# PCB-ARD-BOS2.net
KiCad netlist of a schematic drawn in EAGLE
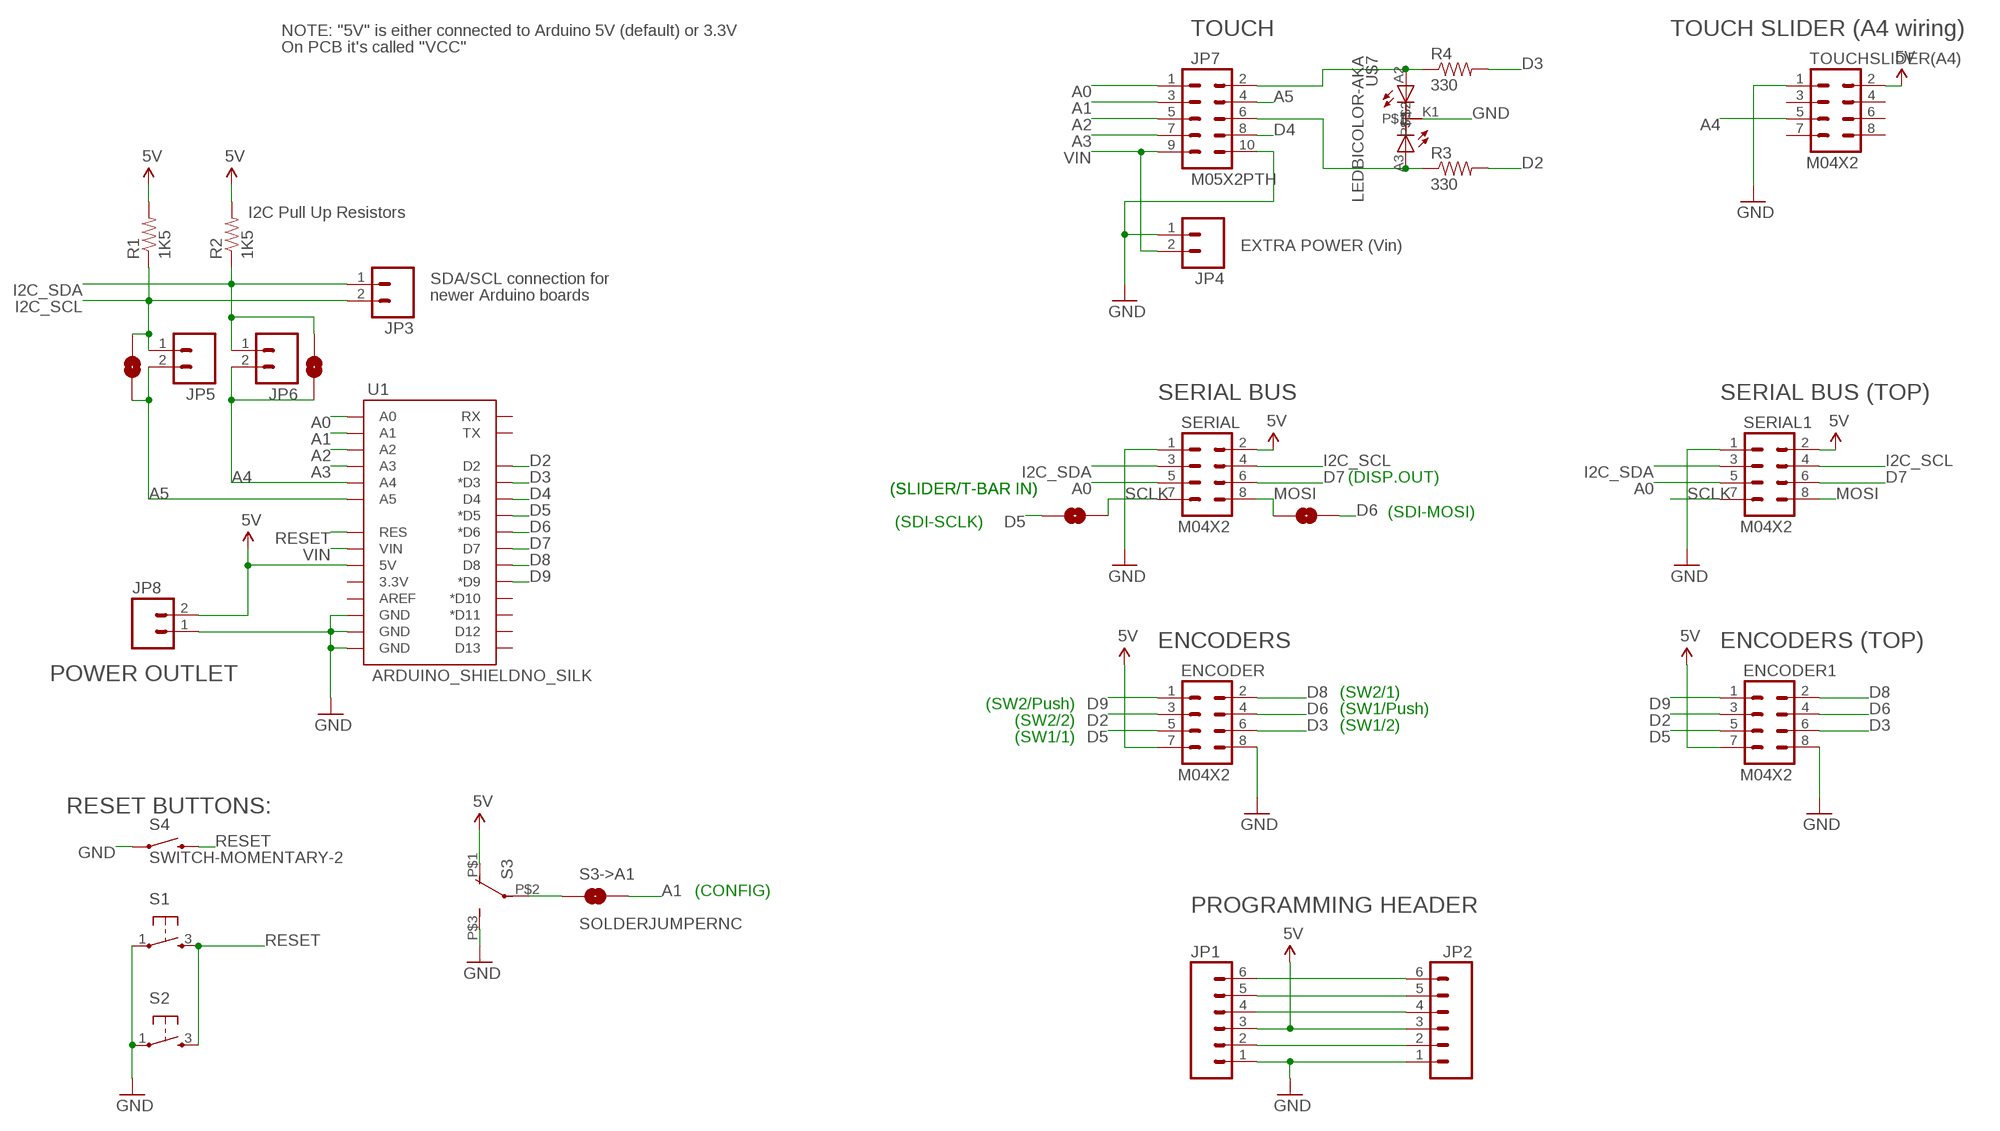
[diagram p0: schematic, sheet 1]

(export (version "E")
  (design (tool "Eeschema 10.0.6"))
  (components
    (comp (ref "ENCODER")
      (value "M04X2")
      (footprint "eagle-import:2X4")
      (libsource (lib "eagle-import") (part "M04X2"))
    )
    (comp (ref "ENCODER1")
      (value "M04X2")
      (footprint "eagle-import:2X4")
      (libsource (lib "eagle-import") (part "M04X2"))
    )
    (comp (ref "JP1")
      (value "M06POLAR")
      (footprint "eagle-import:MOLEX-1X6")
      (libsource (lib "eagle-import") (part "M06POLAR"))
    )
    (comp (ref "JP2")
      (value "M06POLAR")
      (footprint "eagle-import:MOLEX-1X6")
      (libsource (lib "eagle-import") (part "M06POLAR"))
    )
    (comp (ref "JP3")
      (value "M02PTH")
      (footprint "eagle-import:1X02")
      (libsource (lib "eagle-import") (part "M02PTH"))
    )
    (comp (ref "JP4")
      (value "M02PTH")
      (footprint "eagle-import:1X02")
      (libsource (lib "eagle-import") (part "M02PTH"))
    )
    (comp (ref "JP5")
      (value "M02PTH")
      (footprint "eagle-import:1X02")
      (libsource (lib "eagle-import") (part "M02PTH"))
    )
    (comp (ref "JP6")
      (value "M02PTH")
      (footprint "eagle-import:1X02")
      (libsource (lib "eagle-import") (part "M02PTH"))
    )
    (comp (ref "JP7")
      (value "M05X2PTH")
      (footprint "eagle-import:AVR_ICSP")
      (libsource (lib "eagle-import") (part "M05X2PTH"))
    )
    (comp (ref "JP8")
      (value "M02PTH4")
      (footprint "eagle-import:1X02_XTRA_BIG")
      (libsource (lib "eagle-import") (part "M02PTH4"))
    )
    (comp (ref "MOSI->D6")
      (value "SOLDERJUMPERNC")
      (footprint "eagle-import:SJ_2S")
      (libsource (lib "eagle-import") (part "SOLDERJUMPERNC"))
    )
    (comp (ref "R1")
      (value "1K5")
      (footprint "eagle-import:0603-RES")
      (libsource (lib "eagle-import") (part "RESISTOR0603-RES"))
    )
    (comp (ref "R2")
      (value "1K5")
      (footprint "eagle-import:0603-RES")
      (libsource (lib "eagle-import") (part "RESISTOR0603-RES"))
    )
    (comp (ref "R3")
      (value "330")
      (footprint "eagle-import:AXIAL-0.4")
      (libsource (lib "eagle-import") (part "RESISTORPTH-1/4W"))
    )
    (comp (ref "R4")
      (value "330")
      (footprint "eagle-import:AXIAL-0.4")
      (libsource (lib "eagle-import") (part "RESISTORPTH-1/4W"))
    )
    (comp (ref "S1")
      (value "TAC_SWITCH")
      (footprint "eagle-import:PUSHBUTTON")
      (libsource (lib "eagle-import") (part "TAC_SWITCH"))
    )
    (comp (ref "S2")
      (value "TAC_SWITCH")
      (footprint "eagle-import:PUSHBUTTON")
      (libsource (lib "eagle-import") (part "TAC_SWITCH"))
    )
    (comp (ref "S3")
      (value "SWITCH-DPST")
      (footprint "eagle-import:TECONNECTIVITY-DPST")
      (libsource (lib "eagle-import") (part "SWITCH-DPST"))
    )
    (comp (ref "S3->A1")
      (value "SOLDERJUMPERNC")
      (footprint "eagle-import:SJ_2S")
      (libsource (lib "eagle-import") (part "SOLDERJUMPERNC"))
    )
    (comp (ref "S3->A2")
      (value "SOLDERJUMPERNC")
      (footprint "eagle-import:SJ_2S")
      (libsource (lib "eagle-import") (part "SOLDERJUMPERNC"))
    )
    (comp (ref "S3->A3")
      (value "SOLDERJUMPERNC")
      (footprint "eagle-import:SJ_2S")
      (libsource (lib "eagle-import") (part "SOLDERJUMPERNC"))
    )
    (comp (ref "S4")
      (value "SWITCH-MOMENTARY-2")
      (footprint "eagle-import:TACTILE_SWITCH_TALL")
      (libsource (lib "eagle-import") (part "SWITCH-MOMENTARY-2"))
    )
    (comp (ref "SCLK->D5")
      (value "SOLDERJUMPERNC")
      (footprint "eagle-import:SJ_2S")
      (libsource (lib "eagle-import") (part "SOLDERJUMPERNC"))
    )
    (comp (ref "SERIAL")
      (value "M04X2")
      (footprint "eagle-import:2X4")
      (libsource (lib "eagle-import") (part "M04X2"))
    )
    (comp (ref "SERIAL1")
      (value "M04X2")
      (footprint "eagle-import:2X4")
      (libsource (lib "eagle-import") (part "M04X2"))
    )
    (comp (ref "TOUCHSLIDER(A4)")
      (value "M04X2")
      (footprint "eagle-import:2X4")
      (libsource (lib "eagle-import") (part "M04X2"))
    )
    (comp (ref "U$7")
      (value "LEDBICOLOR-AKA")
      (footprint "eagle-import:LED5MM-BICOLOR")
      (libsource (lib "eagle-import") (part "LEDBICOLOR-AKA"))
    )
    (comp (ref "U1")
      (value "ARDUINO_SHIELDNO_SILK")
      (footprint "eagle-import:DUEMILANOVE_VIAS")
      (libsource (lib "eagle-import") (part "ARDUINO_SHIELDNO_SILK"))
    )
  )
  (nets
    (net (code "1") (name "/A0") (class "Default")
      (node (ref "JP7") (pin "1") (pinfunction "1_1") (pintype "passive"))
      (node (ref "SERIAL") (pin "5") (pinfunction "5_5") (pintype "passive"))
      (node (ref "SERIAL1") (pin "5") (pinfunction "5_5") (pintype "passive"))
      (node (ref "U1") (pin "A0") (pinfunction "A0_A0") (pintype "bidirectional"))
    )
    (net (code "2") (name "/A1") (class "Default")
      (node (ref "JP7") (pin "3") (pinfunction "3_3") (pintype "passive"))
      (node (ref "S3->A1") (pin "2") (pinfunction "2_2") (pintype "passive"))
      (node (ref "U1") (pin "A1") (pinfunction "A1_A1") (pintype "bidirectional"))
    )
    (net (code "3") (name "/A2") (class "Default")
      (node (ref "JP7") (pin "5") (pinfunction "5_5") (pintype "passive"))
      (node (ref "U1") (pin "A2") (pinfunction "A2_A2") (pintype "bidirectional"))
    )
    (net (code "4") (name "/A3") (class "Default")
      (node (ref "JP7") (pin "7") (pinfunction "7_7") (pintype "passive"))
      (node (ref "U1") (pin "A3") (pinfunction "A3_A3") (pintype "bidirectional"))
    )
    (net (code "5") (name "/A4") (class "Default")
      (node (ref "JP6") (pin "2") (pinfunction "2_2") (pintype "passive"))
      (node (ref "S3->A3") (pin "2") (pinfunction "2_2") (pintype "passive"))
      (node (ref "TOUCHSLIDER(A4)") (pin "5") (pinfunction "5_5") (pintype "passive"))
      (node (ref "U1") (pin "A4") (pinfunction "A4_A4") (pintype "bidirectional"))
    )
    (net (code "6") (name "/A5") (class "Default")
      (node (ref "JP5") (pin "2") (pinfunction "2_2") (pintype "passive"))
      (node (ref "JP7") (pin "4") (pinfunction "4_4") (pintype "passive"))
      (node (ref "S3->A2") (pin "2") (pinfunction "2_2") (pintype "passive"))
      (node (ref "U1") (pin "A5") (pinfunction "A5_A5") (pintype "bidirectional"))
    )
    (net (code "7") (name "/D2") (class "Default")
      (node (ref "ENCODER") (pin "3") (pinfunction "3_3") (pintype "passive"))
      (node (ref "ENCODER1") (pin "3") (pinfunction "3_3") (pintype "passive"))
      (node (ref "R3") (pin "P$2") (pinfunction "2_P$2") (pintype "passive"))
      (node (ref "U1") (pin "D2") (pinfunction "D2_D2") (pintype "bidirectional"))
    )
    (net (code "8") (name "/D3") (class "Default")
      (node (ref "ENCODER") (pin "6") (pinfunction "6_6") (pintype "passive"))
      (node (ref "ENCODER1") (pin "6") (pinfunction "6_6") (pintype "passive"))
      (node (ref "R4") (pin "P$2") (pinfunction "2_P$2") (pintype "passive"))
      (node (ref "U1") (pin "D3") (pinfunction "*D3_D3") (pintype "bidirectional"))
    )
    (net (code "9") (name "/D4") (class "Default")
      (node (ref "JP7") (pin "8") (pinfunction "8_8") (pintype "passive"))
      (node (ref "U1") (pin "D4") (pinfunction "D4_D4") (pintype "bidirectional"))
    )
    (net (code "10") (name "/D5") (class "Default")
      (node (ref "ENCODER") (pin "5") (pinfunction "5_5") (pintype "passive"))
      (node (ref "ENCODER1") (pin "5") (pinfunction "5_5") (pintype "passive"))
      (node (ref "SCLK->D5") (pin "1") (pinfunction "1_1") (pintype "passive"))
      (node (ref "U1") (pin "D5") (pinfunction "*D5_D5") (pintype "bidirectional"))
    )
    (net (code "11") (name "/D6") (class "Default")
      (node (ref "ENCODER") (pin "4") (pinfunction "4_4") (pintype "passive"))
      (node (ref "ENCODER1") (pin "4") (pinfunction "4_4") (pintype "passive"))
      (node (ref "MOSI->D6") (pin "2") (pinfunction "2_2") (pintype "passive"))
      (node (ref "U1") (pin "D6") (pinfunction "*D6_D6") (pintype "bidirectional"))
    )
    (net (code "12") (name "/D7") (class "Default")
      (node (ref "SERIAL") (pin "6") (pinfunction "6_6") (pintype "passive"))
      (node (ref "SERIAL1") (pin "6") (pinfunction "6_6") (pintype "passive"))
      (node (ref "U1") (pin "D7") (pinfunction "D7_D7") (pintype "bidirectional"))
    )
    (net (code "13") (name "/D8") (class "Default")
      (node (ref "ENCODER") (pin "2") (pinfunction "2_2") (pintype "passive"))
      (node (ref "ENCODER1") (pin "2") (pinfunction "2_2") (pintype "passive"))
      (node (ref "U1") (pin "D8") (pinfunction "D8_D8") (pintype "bidirectional"))
    )
    (net (code "14") (name "/D9") (class "Default")
      (node (ref "ENCODER") (pin "1") (pinfunction "1_1") (pintype "passive"))
      (node (ref "ENCODER1") (pin "1") (pinfunction "1_1") (pintype "passive"))
      (node (ref "U1") (pin "D9") (pinfunction "*D9_D9") (pintype "bidirectional"))
    )
    (net (code "15") (name "/I2C_SCL") (class "Default")
      (node (ref "JP3") (pin "2") (pinfunction "2_2") (pintype "passive"))
      (node (ref "JP5") (pin "1") (pinfunction "1_1") (pintype "passive"))
      (node (ref "R1") (pin "1") (pinfunction "1_1") (pintype "passive"))
      (node (ref "S3->A2") (pin "1") (pinfunction "1_1") (pintype "passive"))
      (node (ref "SERIAL") (pin "4") (pinfunction "4_4") (pintype "passive"))
      (node (ref "SERIAL1") (pin "4") (pinfunction "4_4") (pintype "passive"))
    )
    (net (code "16") (name "/I2C_SDA") (class "Default")
      (node (ref "JP3") (pin "1") (pinfunction "1_1") (pintype "passive"))
      (node (ref "JP6") (pin "1") (pinfunction "1_1") (pintype "passive"))
      (node (ref "R2") (pin "1") (pinfunction "1_1") (pintype "passive"))
      (node (ref "S3->A3") (pin "1") (pinfunction "1_1") (pintype "passive"))
      (node (ref "SERIAL") (pin "3") (pinfunction "3_3") (pintype "passive"))
      (node (ref "SERIAL1") (pin "3") (pinfunction "3_3") (pintype "passive"))
    )
    (net (code "17") (name "/MOSI") (class "Default")
      (node (ref "MOSI->D6") (pin "1") (pinfunction "1_1") (pintype "passive"))
      (node (ref "SERIAL") (pin "8") (pinfunction "8_8") (pintype "passive"))
      (node (ref "SERIAL1") (pin "8") (pinfunction "8_8") (pintype "passive"))
    )
    (net (code "18") (name "/RESET") (class "Default")
      (node (ref "S1") (pin "3") (pinfunction "3_3") (pintype "passive"))
      (node (ref "S2") (pin "3") (pinfunction "3_3") (pintype "passive"))
      (node (ref "S4") (pin "B2") (pinfunction "2_B2") (pintype "passive"))
      (node (ref "U1") (pin "RES") (pinfunction "RES_RES") (pintype "bidirectional"))
    )
    (net (code "19") (name "/SCLK") (class "Default")
      (node (ref "SCLK->D5") (pin "2") (pinfunction "2_2") (pintype "passive"))
      (node (ref "SERIAL") (pin "7") (pinfunction "7_7") (pintype "passive"))
      (node (ref "SERIAL1") (pin "7") (pinfunction "7_7") (pintype "passive"))
    )
    (net (code "20") (name "/VIN") (class "Default")
      (node (ref "JP4") (pin "2") (pinfunction "2_2") (pintype "passive"))
      (node (ref "JP7") (pin "9") (pinfunction "9_9") (pintype "passive"))
      (node (ref "U1") (pin "VIN") (pinfunction "VIN_VIN") (pintype "bidirectional"))
    )
    (net (code "21") (name "5V") (class "Default")
      (node (ref "ENCODER") (pin "7") (pinfunction "7_7") (pintype "passive"))
      (node (ref "ENCODER1") (pin "7") (pinfunction "7_7") (pintype "passive"))
      (node (ref "JP1") (pin "3") (pinfunction "3_3") (pintype "passive"))
      (node (ref "JP2") (pin "3") (pinfunction "3_3") (pintype "passive"))
      (node (ref "JP8") (pin "2") (pinfunction "2_2") (pintype "passive"))
      (node (ref "R1") (pin "2") (pinfunction "2_2") (pintype "passive"))
      (node (ref "R2") (pin "2") (pinfunction "2_2") (pintype "passive"))
      (node (ref "S3") (pin "P$1") (pinfunction "O_P$1") (pintype "passive"))
      (node (ref "SERIAL") (pin "2") (pinfunction "2_2") (pintype "passive"))
      (node (ref "SERIAL1") (pin "2") (pinfunction "2_2") (pintype "passive"))
      (node (ref "TOUCHSLIDER(A4)") (pin "2") (pinfunction "2_2") (pintype "passive"))
      (node (ref "U1") (pin "5V") (pinfunction "5V_5V") (pintype "bidirectional"))
    )
    (net (code "22") (name "GND") (class "Default")
      (node (ref "ENCODER") (pin "8") (pinfunction "8_8") (pintype "passive"))
      (node (ref "ENCODER1") (pin "8") (pinfunction "8_8") (pintype "passive"))
      (node (ref "JP1") (pin "1") (pinfunction "1_1") (pintype "passive"))
      (node (ref "JP2") (pin "1") (pinfunction "1_1") (pintype "passive"))
      (node (ref "JP4") (pin "1") (pinfunction "1_1") (pintype "passive"))
      (node (ref "JP7") (pin "10") (pinfunction "10_10") (pintype "passive"))
      (node (ref "JP8") (pin "1") (pinfunction "1_1") (pintype "passive"))
      (node (ref "S1") (pin "1") (pinfunction "1_1") (pintype "passive"))
      (node (ref "S2") (pin "1") (pinfunction "1_1") (pintype "passive"))
      (node (ref "S3") (pin "P$3") (pinfunction "S_P$3") (pintype "passive"))
      (node (ref "S4") (pin "A2") (pinfunction "1_A2") (pintype "passive"))
      (node (ref "SERIAL") (pin "1") (pinfunction "1_1") (pintype "passive"))
      (node (ref "SERIAL1") (pin "1") (pinfunction "1_1") (pintype "passive"))
      (node (ref "TOUCHSLIDER(A4)") (pin "1") (pinfunction "1_1") (pintype "passive"))
      (node (ref "U$7") (pin "K1") (pinfunction "P$1_K1") (pintype "bidirectional"))
      (node (ref "U1") (pin "GND@0") (pinfunction "GND_GND@0") (pintype "bidirectional"))
      (node (ref "U1") (pin "GND@1") (pinfunction "GND_GND@1") (pintype "bidirectional"))
      (node (ref "U1") (pin "GND@2") (pinfunction "GND_GND@2") (pintype "bidirectional"))
    )
    (net (code "23") (name "Net-(JP1-Pad2)") (class "Default")
      (node (ref "JP1") (pin "2") (pinfunction "2_2") (pintype "passive"))
      (node (ref "JP2") (pin "2") (pinfunction "2_2") (pintype "passive"))
    )
    (net (code "24") (name "Net-(JP1-Pad4)") (class "Default")
      (node (ref "JP1") (pin "4") (pinfunction "4_4") (pintype "passive"))
      (node (ref "JP2") (pin "4") (pinfunction "4_4") (pintype "passive"))
    )
    (net (code "25") (name "Net-(JP1-Pad5)") (class "Default")
      (node (ref "JP1") (pin "5") (pinfunction "5_5") (pintype "passive"))
      (node (ref "JP2") (pin "5") (pinfunction "5_5") (pintype "passive"))
    )
    (net (code "26") (name "Net-(JP1-Pad6)") (class "Default")
      (node (ref "JP1") (pin "6") (pinfunction "6_6") (pintype "passive"))
      (node (ref "JP2") (pin "6") (pinfunction "6_6") (pintype "passive"))
    )
    (net (code "27") (name "Net-(R3-1)") (class "Default")
      (node (ref "JP7") (pin "6") (pinfunction "6_6") (pintype "passive"))
      (node (ref "R3") (pin "P$1") (pinfunction "1_P$1") (pintype "passive"))
      (node (ref "U$7") (pin "A3") (pinfunction "P$3_A3") (pintype "bidirectional"))
    )
    (net (code "28") (name "Net-(R4-1)") (class "Default")
      (node (ref "JP7") (pin "2") (pinfunction "2_2") (pintype "passive"))
      (node (ref "R4") (pin "P$1") (pinfunction "1_P$1") (pintype "passive"))
      (node (ref "U$7") (pin "A2") (pinfunction "P$2_A2") (pintype "bidirectional"))
    )
    (net (code "29") (name "Net-(S3-P)") (class "Default")
      (node (ref "S3") (pin "P$2") (pinfunction "P_P$2") (pintype "passive"))
      (node (ref "S3->A1") (pin "1") (pinfunction "1_1") (pintype "passive"))
    )
    (net (code "30") (name "unconnected-(TOUCHSLIDER(A4)-Pad3)") (class "Default")
      (node (ref "TOUCHSLIDER(A4)") (pin "3") (pinfunction "3_3") (pintype "passive"))
    )
    (net (code "31") (name "unconnected-(TOUCHSLIDER(A4)-Pad4)") (class "Default")
      (node (ref "TOUCHSLIDER(A4)") (pin "4") (pinfunction "4_4") (pintype "passive"))
    )
    (net (code "32") (name "unconnected-(TOUCHSLIDER(A4)-Pad6)") (class "Default")
      (node (ref "TOUCHSLIDER(A4)") (pin "6") (pinfunction "6_6") (pintype "passive"))
    )
    (net (code "33") (name "unconnected-(TOUCHSLIDER(A4)-Pad7)") (class "Default")
      (node (ref "TOUCHSLIDER(A4)") (pin "7") (pinfunction "7_7") (pintype "passive"))
    )
    (net (code "34") (name "unconnected-(TOUCHSLIDER(A4)-Pad8)") (class "Default")
      (node (ref "TOUCHSLIDER(A4)") (pin "8") (pinfunction "8_8") (pintype "passive"))
    )
    (net (code "35") (name "unconnected-(U1-*D10-PadD10)") (class "Default")
      (node (ref "U1") (pin "D10") (pinfunction "*D10_D10") (pintype "bidirectional"))
    )
    (net (code "36") (name "unconnected-(U1-*D11-PadD11)") (class "Default")
      (node (ref "U1") (pin "D11") (pinfunction "*D11_D11") (pintype "bidirectional"))
    )
    (net (code "37") (name "unconnected-(U1-Pad3.3V)") (class "Default")
      (node (ref "U1") (pin "3.3V") (pinfunction "3.3V_3.3V") (pintype "bidirectional"))
    )
    (net (code "38") (name "unconnected-(U1-PadAREF)") (class "Default")
      (node (ref "U1") (pin "AREF") (pinfunction "AREF_AREF") (pintype "bidirectional"))
    )
    (net (code "39") (name "unconnected-(U1-PadD12)") (class "Default")
      (node (ref "U1") (pin "D12") (pinfunction "D12_D12") (pintype "bidirectional"))
    )
    (net (code "40") (name "unconnected-(U1-PadD13)") (class "Default")
      (node (ref "U1") (pin "D13") (pinfunction "D13_D13") (pintype "bidirectional"))
    )
    (net (code "41") (name "unconnected-(U1-PadRX)") (class "Default")
      (node (ref "U1") (pin "RX") (pinfunction "RX_RX") (pintype "bidirectional"))
    )
    (net (code "42") (name "unconnected-(U1-PadTX)") (class "Default")
      (node (ref "U1") (pin "TX") (pinfunction "TX_TX") (pintype "bidirectional"))
    )
  )
)
